# 3_MCU_EPS.net
KiCad netlist of a schematic drawn in Altium Designer
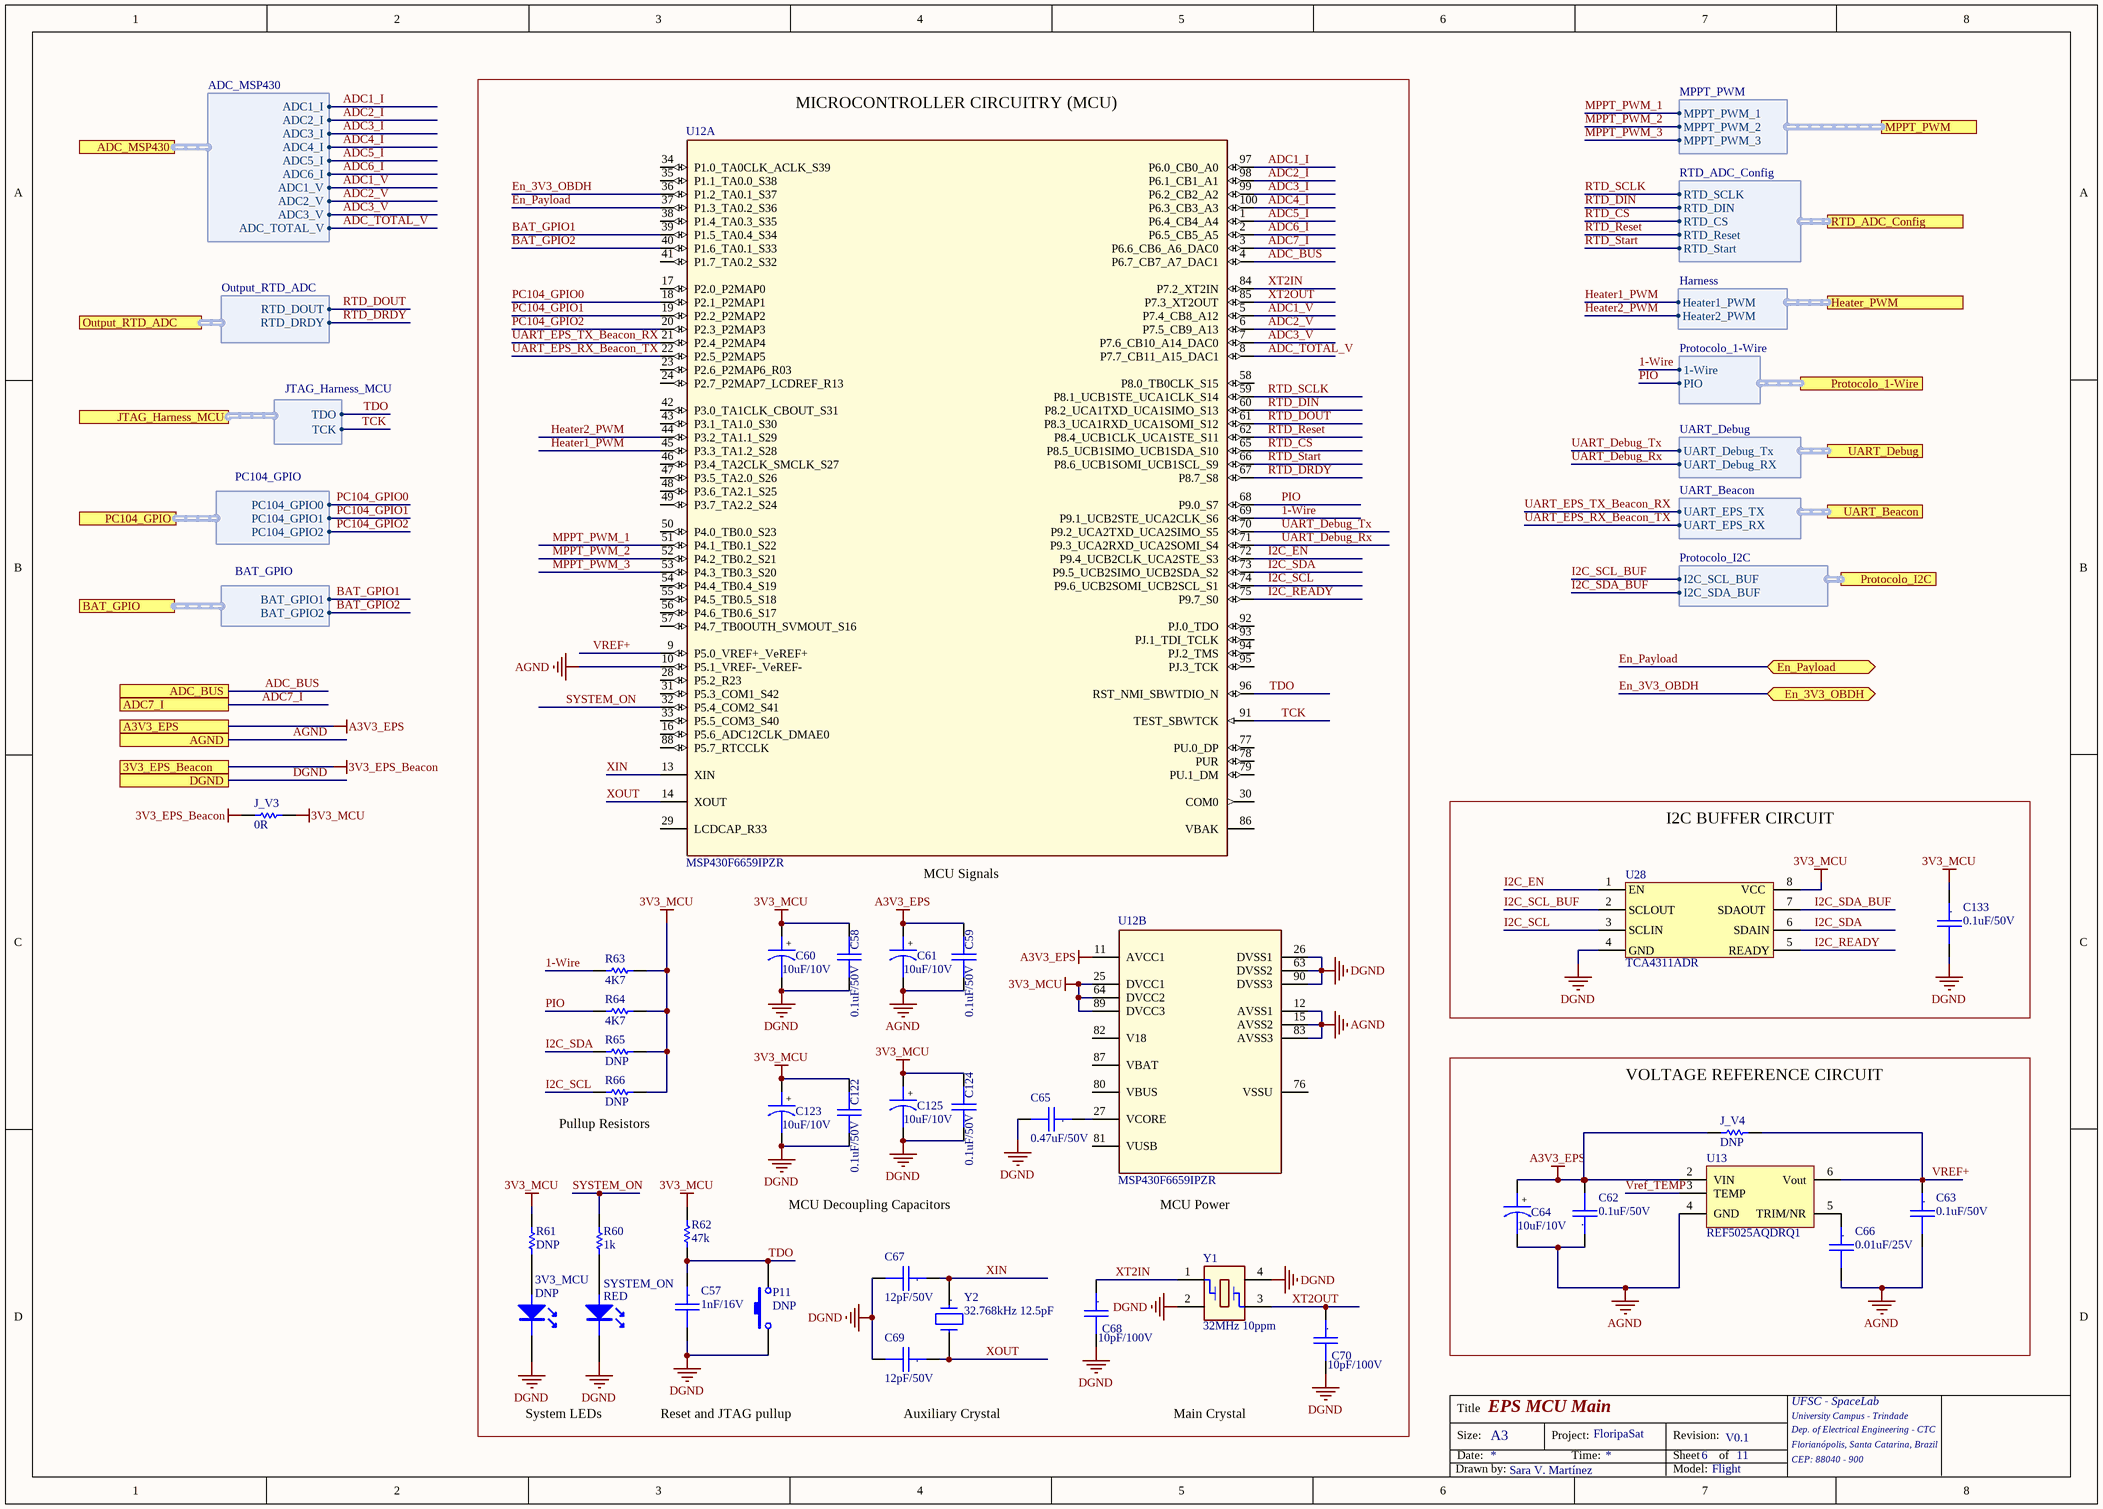
[diagram p0: 3_MCU_EPS.SchDoc]

(export (version "E")
  (design (tool "Eeschema 10.0.6"))
  (components
    (comp (ref "3V3_MCU")
      (value "DNP")
      (footprint "0603-LED")
      (description "SMD Green LED")
      (fields (field (name "PARTNUMBER") "150060VS75000"))
      (libsource (lib "FloripaSatSchlib") (part "LED/G_0603"))
    )
    (comp (ref "C57")
      (value "1nF/16V")
      (footprint "CC0805")
      (description "CAP CER 1nF 16V 0603 5%")
      (fields (field (name "PARTNUMBER") "C0603X102J4RECAUTO"))
      (libsource (lib "OBDH_Eng_Model_2_ALT") (part "Cap_Cer_X7R_1nF_16V_0603"))
    )
    (comp (ref "C58")
      (value "0.1uF/50V")
      (footprint "CC0603")
      (description "CAP CER 0.1UF 50V 10% X7R 0603")
      (fields (field (name "PARTNUMBER") "CC0603KPX7R9BB104"))
      (libsource (lib "PCB_Project_FlightModel_EPS") (part "Cap_Cer_X7R_0.1uF_50V_0603"))
    )
    (comp (ref "C59")
      (value "0.1uF/50V")
      (footprint "CC0603")
      (description "CAP CER 0.1UF 50V 10% X7R 0603")
      (fields (field (name "PARTNUMBER") "CC0603KPX7R9BB104"))
      (libsource (lib "PCB_Project_FlightModel_EPS") (part "Cap_Cer_X7R_0.1uF_50V_0603"))
    )
    (comp (ref "C60")
      (value "10uF/10V")
      (footprint "FloripaSatPcbLib:CC0805_Tantalum")
      (description "CAP Tantalum 10uF 6.3V 10% 0805")
      (fields (field (name "PARTNUMBER") "TPSR106K006R1000"))
      (libsource (lib "FloripaSatSchlib") (part "Cap_Tant_SMD_10uF_6V3_0805"))
    )
    (comp (ref "C61")
      (value "10uF/10V")
      (footprint "FloripaSatPcbLib:CC0805_Tantalum")
      (description "CAP Tantalum 10uF 6.3V 10% 0805")
      (fields (field (name "PARTNUMBER") "TPSR106K006R1000"))
      (libsource (lib "FloripaSatSchlib") (part "Cap_Tant_SMD_10uF_6V3_0805"))
    )
    (comp (ref "C62")
      (value "0.1uF/50V")
      (footprint "CC0805")
      (description "CAP CER 0.1UF 50V 10% X7R 0805")
      (fields (field (name "PARTNUMBER") "GRM188R71H104KA93D"))
      (libsource (lib "FloripaSatSchlib") (part "Cap_Cer_X7R_0.1uF_25V_0805"))
    )
    (comp (ref "C63")
      (value "0.1uF/50V")
      (footprint "CC0603")
      (description "CAP CER 0.1UF 50V 10% X7R 0603")
      (fields (field (name "PARTNUMBER") "CC0603KPX7R9BB104"))
      (libsource (lib "PCB_Project_FlightModel_EPS") (part "Cap_Cer_X7R_0.1uF_50V_0603"))
    )
    (comp (ref "C64")
      (value "10uF/10V")
      (footprint "FloripaSatPcbLib:CC0805_Tantalum")
      (description "CAP Tantalum 10uF 6.3V 10% 0805")
      (fields (field (name "PARTNUMBER") "TPSR106K006R1000"))
      (libsource (lib "FloripaSatSchlib") (part "Cap_Tant_SMD_10uF_6V3_0805"))
    )
    (comp (ref "C65")
      (value "0.47uF/50V")
      (footprint "CC0603")
      (description "CAP CER 0.47UF 50V 10% X7R 0603")
      (fields (field (name "PARTNUMBER") "C1608X7R1H474K080AE"))
      (libsource (lib "FloripaSatSchlib") (part "Cap_Cer_X7R_0.47uF_50V_0603"))
    )
    (comp (ref "C66")
      (value "0.01uF/25V")
      (footprint "CC0603")
      (description "CAP CER 0.01UF 25V 5% X7R 0603")
      (fields (field (name "PARTNUMBER") "06033C103JAT4A"))
      (libsource (lib "FloripaSatSchlib") (part "Cap_Cer_X7R_0.01uF_25V_0603"))
    )
    (comp (ref "C67")
      (value "12pF/50V")
      (footprint "CC0603")
      (description "CAP CER 12pF 50V 0603")
      (fields (field (name "PARTNUMBER") "GQM1885C1H120GB01D"))
      (libsource (lib "FloripaSatSchlib") (part "Cap_Cer_X7R_12pF_50V_0603"))
    )
    (comp (ref "C68")
      (value "10pF/100V")
      (footprint "CC0805")
      (description "CAP CER 10pF 100V 0805")
      (fields (field (name "PARTNUMBER") "08051A100FAT2A"))
      (libsource (lib "FloripaSatSchlib") (part "Cap_Cer_X7R_10pF_100V_0805"))
    )
    (comp (ref "C69")
      (value "12pF/50V")
      (footprint "CC0603")
      (description "CAP CER 12pF 50V 0603")
      (fields (field (name "PARTNUMBER") "GQM1885C1H120GB01D"))
      (libsource (lib "FloripaSatSchlib") (part "Cap_Cer_X7R_12pF_50V_0603"))
    )
    (comp (ref "C70")
      (value "10pF/100V")
      (footprint "CC0805")
      (description "CAP CER 10pF 100V 0805")
      (fields (field (name "PARTNUMBER") "08051A100FAT2A"))
      (libsource (lib "FloripaSatSchlib") (part "Cap_Cer_X7R_10pF_100V_0805"))
    )
    (comp (ref "C122")
      (value "0.1uF/50V")
      (footprint "CC0603")
      (description "CAP CER 0.1UF 50V 10% X7R 0603")
      (fields (field (name "PARTNUMBER") "CC0603KPX7R9BB104"))
      (libsource (lib "PCB_Project_FlightModel_EPS") (part "Cap_Cer_X7R_0.1uF_50V_0603"))
    )
    (comp (ref "C123")
      (value "10uF/10V")
      (footprint "FloripaSatPcbLib:CC0805_Tantalum")
      (description "CAP Tantalum 10uF 6.3V 10% 0805")
      (fields (field (name "PARTNUMBER") "TPSR106K006R1000"))
      (libsource (lib "FloripaSatSchlib") (part "Cap_Tant_SMD_10uF_6V3_0805"))
    )
    (comp (ref "C124")
      (value "0.1uF/50V")
      (footprint "CC0603")
      (description "CAP CER 0.1UF 50V 10% X7R 0603")
      (fields (field (name "PARTNUMBER") "CC0603KPX7R9BB104"))
      (libsource (lib "PCB_Project_FlightModel_EPS") (part "Cap_Cer_X7R_0.1uF_50V_0603"))
    )
    (comp (ref "C125")
      (value "10uF/10V")
      (footprint "FloripaSatPcbLib:CC0805_Tantalum")
      (description "CAP Tantalum 10uF 6.3V 10% 0805")
      (fields (field (name "PARTNUMBER") "TPSR106K006R1000"))
      (libsource (lib "FloripaSatSchlib") (part "Cap_Tant_SMD_10uF_6V3_0805"))
    )
    (comp (ref "C133")
      (value "0.1uF/50V")
      (footprint "CC0603")
      (description "CAP CER 0.1UF 50V 10% X7R 0603")
      (fields (field (name "PARTNUMBER") "CC0603KPX7R9BB104"))
      (libsource (lib "PCB_Project_FlightModel_EPS") (part "Cap_Cer_X7R_0.1uF_50V_0603"))
    )
    (comp (ref "J_V3")
      (value "0R")
      (footprint "0805")
      (description "RES 0R OHM 1/8W JUMPER 0805")
      (fields (field (name "PARTNUMBER") "CRCW08050000Z0EA"))
      (libsource (lib "PCB_Project_FlightModel_EPS") (part "R0R_JUMPER_1/8W_0805"))
    )
    (comp (ref "J_V4")
      (value "DNP")
      (footprint "0805")
      (description "RES 0R OHM 1/8W JUMPER 0805")
      (fields (field (name "PARTNUMBER") "CRCW08050000Z0EA"))
      (libsource (lib "PCB_Project_FlightModel_EPS") (part "R0R_JUMPER_1/8W_0805"))
    )
    (comp (ref "P11")
      (value "DNP")
      (footprint "B3U-1000P")
      (description "Tactile Switch SPST-NO Top Actuated Surface Mount 12V 0.05A")
      (fields (field (name "PARTNUMBER") "B3U-1000P") (field (name "MANUFACTURER") "TE Connectivity"))
      (libsource (lib "PCB_Project_FlightModel_EPS") (part "Tactile_Switches_B3U-1000P"))
    )
    (comp (ref "R60")
      (value "1k")
      (footprint "0603")
      (description "RES 1.0K OHM 1/8W 1% 0603")
      (fields (field (name "PARTNUMBER") "MCT06030C1001FP500"))
      (libsource (lib "FloripaSatSchlib") (part "R1.0k_1%_1/8W_0603"))
    )
    (comp (ref "R61")
      (value "DNP")
      (footprint "0603")
      (description "RES 1.0K OHM 1/8W 1% 0603")
      (fields (field (name "PARTNUMBER") "MCT06030C1001FP500"))
      (libsource (lib "FloripaSatSchlib") (part "R1.0k_1%_1/8W_0603"))
    )
    (comp (ref "R62")
      (value "47k")
      (footprint "0603")
      (description "RES 47K OHM 1/8W 0.5% 0603")
      (fields (field (name "PARTNUMBER") "MCT0603MD4702DP500"))
      (libsource (lib "FloripaSatSchlib") (part "R47k_1%_1/8W_0603"))
    )
    (comp (ref "R63")
      (value "4K7")
      (footprint "0603")
      (description "RES 4K7 OHM 1/8W 1% 0603")
      (fields (field (name "PARTNUMBER") "MCT06030C4701FP500"))
      (libsource (lib "FloripaSatSchlib") (part "R4.7K_1%_1/8W_0603"))
    )
    (comp (ref "R64")
      (value "4K7")
      (footprint "0603")
      (description "RES 4K7 OHM 1/8W 1% 0603")
      (fields (field (name "PARTNUMBER") "MCT06030C4701FP500"))
      (libsource (lib "FloripaSatSchlib") (part "R4.7K_1%_1/8W_0603"))
    )
    (comp (ref "R65")
      (value "DNP")
      (footprint "0603")
      (description "RES 10K OHM 1/8W 1%  0603")
      (fields (field (name "PARTNUMBER") "MCT0603MC1002FP500"))
      (libsource (lib "FloripaSatSchlib") (part "R10k_1%_1/8W_0603"))
    )
    (comp (ref "R66")
      (value "DNP")
      (footprint "0603")
      (description "RES 10K OHM 1/8W 1%  0603")
      (fields (field (name "PARTNUMBER") "MCT0603MC1002FP500"))
      (libsource (lib "FloripaSatSchlib") (part "R10k_1%_1/8W_0603"))
    )
    (comp (ref "SYSTEM_ON")
      (value "RED")
      (footprint "0603-LED")
      (description "SMD Red LED")
      (fields (field (name "PARTNUMBER") "LTST-C191KFKT"))
      (libsource (lib "FloripaSatSchlib") (part "LED/R_0603"))
    )
    (comp (ref "U12")
      (value "MSP430F6659IPZR")
      (footprint "PZ0100A_N")
      (description "Imported")
      (fields
        (field (name "ALTERNATE PARTNUMBER") "MSP430F6659IPZ")
        (field (name "MANUFACTURER") "Texas Instruments")
      )
      (libsource (lib "FloripaSatSchlib") (part "MSP430F6659IPZR"))
    )
    (comp (ref "U13")
      (value "REF5025AQDRQ1")
      (footprint "SOIC-8")
      (description "REF5025A-Q1")
      (libsource (lib "FloripaSatSchlib") (part "REF5025A-Q1"))
    )
    (comp (ref "U28")
      (value "TCA4311ADR")
      (footprint "SOIC8")
      (description "IC SIGNAL BUFFER I2C 8SOIC")
      (libsource (lib "PCB_Project_FlightModel_EPS") (part "TCA4311ADR"))
    )
    (comp (ref "Y1")
      (value "32MHz 10ppm")
      (footprint "XTAL_ABM8X")
      (description "32MHz ±10ppm Crystal 10pF 60 Ohm -40°C ~ 125°C")
      (fields (field (name "PARTNUMBER") "ABM8X-102-32.000MHZ-T"))
      (libsource (lib "FloripaSatSchlib") (part "XTAL_32MHz_SMD_4-SMD"))
    )
    (comp (ref "Y2")
      (value "32.768kHz 12.5pF")
      (footprint "ABS06 0805")
      (description "32.768kHz ±20ppm Crystal 12.5pF 70 kOhm -40°C ~ 125°C")
      (fields (field (name "PARTNUMBER") "ECS-.327-12.5-34S-TR"))
      (libsource (lib "FloripaSatSchlib") (part "Xtal_32.768kHz_12pF_2_SMD"))
    )
  )
  (nets
    (net (code "13") (name "/1-Wire") (class "Default")
      (node (ref "R63") (pin "2") (pinfunction "2_2") (pintype "passive"))
      (node (ref "U12") (pin "69") (pinfunction "P9.1_UCB2STE_UCA2CLK_S6_69") (pintype "bidirectional"))
    )
    (net (code "14") (name "/ADC1_I") (class "Default")
      (node (ref "U12") (pin "97") (pinfunction "P6.0_CB0_A0_97") (pintype "bidirectional"))
    )
    (net (code "15") (name "/ADC1_V") (class "Default")
      (node (ref "U12") (pin "5") (pinfunction "P7.4_CB8_A12_5") (pintype "bidirectional"))
    )
    (net (code "16") (name "/ADC2_I") (class "Default")
      (node (ref "U12") (pin "98") (pinfunction "P6.1_CB1_A1_98") (pintype "bidirectional"))
    )
    (net (code "17") (name "/ADC2_V") (class "Default")
      (node (ref "U12") (pin "6") (pinfunction "P7.5_CB9_A13_6") (pintype "bidirectional"))
    )
    (net (code "18") (name "/ADC3_I") (class "Default")
      (node (ref "U12") (pin "99") (pinfunction "P6.2_CB2_A2_99") (pintype "bidirectional"))
    )
    (net (code "19") (name "/ADC3_V") (class "Default")
      (node (ref "U12") (pin "7") (pinfunction "P7.6_CB10_A14_DAC0_7") (pintype "bidirectional"))
    )
    (net (code "20") (name "/ADC4_I") (class "Default")
      (node (ref "U12") (pin "100") (pinfunction "P6.3_CB3_A3_100") (pintype "bidirectional"))
    )
    (net (code "21") (name "/ADC5_I") (class "Default")
      (node (ref "U12") (pin "1") (pinfunction "P6.4_CB4_A4_1") (pintype "bidirectional"))
    )
    (net (code "22") (name "/ADC6_I") (class "Default")
      (node (ref "U12") (pin "2") (pinfunction "P6.5_CB5_A5_2") (pintype "bidirectional"))
    )
    (net (code "23") (name "/ADC7_I") (class "Default")
      (node (ref "U12") (pin "3") (pinfunction "P6.6_CB6_A6_DAC0_3") (pintype "bidirectional"))
    )
    (net (code "24") (name "/ADC_BUS") (class "Default")
      (node (ref "U12") (pin "4") (pinfunction "P6.7_CB7_A7_DAC1_4") (pintype "bidirectional"))
    )
    (net (code "25") (name "/ADC_TOTAL_V") (class "Default")
      (node (ref "U12") (pin "8") (pinfunction "P7.7_CB11_A15_DAC1_8") (pintype "bidirectional"))
    )
    (net (code "26") (name "/BAT_GPIO1") (class "Default")
      (node (ref "U12") (pin "39") (pinfunction "P1.5_TA0.4_S34_39") (pintype "bidirectional"))
    )
    (net (code "27") (name "/BAT_GPIO2") (class "Default")
      (node (ref "U12") (pin "40") (pinfunction "P1.6_TA0.1_S33_40") (pintype "bidirectional"))
    )
    (net (code "28") (name "/En_3V3_OBDH") (class "Default")
      (node (ref "U12") (pin "36") (pinfunction "P1.2_TA0.1_S37_36") (pintype "bidirectional"))
    )
    (net (code "29") (name "/En_Payload") (class "Default")
      (node (ref "U12") (pin "37") (pinfunction "P1.3_TA0.2_S36_37") (pintype "bidirectional"))
    )
    (net (code "30") (name "/Heater1_PWM") (class "Default")
      (node (ref "U12") (pin "45") (pinfunction "P3.3_TA1.2_S28_45") (pintype "bidirectional"))
    )
    (net (code "31") (name "/Heater2_PWM") (class "Default")
      (node (ref "U12") (pin "44") (pinfunction "P3.2_TA1.1_S29_44") (pintype "bidirectional"))
    )
    (net (code "32") (name "/I2C_EN") (class "Default")
      (node (ref "U12") (pin "72") (pinfunction "P9.4_UCB2CLK_UCA2STE_S3_72") (pintype "bidirectional"))
      (node (ref "U28") (pin "1") (pinfunction "EN_1") (pintype "passive"))
    )
    (net (code "33") (name "/I2C_READY") (class "Default")
      (node (ref "U12") (pin "75") (pinfunction "P9.7_S0_75") (pintype "bidirectional"))
      (node (ref "U28") (pin "5") (pinfunction "READY_5") (pintype "passive"))
    )
    (net (code "34") (name "/I2C_SCL") (class "Default")
      (node (ref "R66") (pin "2") (pinfunction "2_2") (pintype "passive"))
      (node (ref "U12") (pin "74") (pinfunction "P9.6_UCB2SOMI_UCB2SCL_S1_74") (pintype "bidirectional"))
      (node (ref "U28") (pin "3") (pinfunction "SCLIN_3") (pintype "passive"))
    )
    (net (code "35") (name "/I2C_SCL_BUF") (class "Default")
      (node (ref "U28") (pin "2") (pinfunction "SCLOUT_2") (pintype "passive"))
    )
    (net (code "36") (name "/I2C_SDA") (class "Default")
      (node (ref "R65") (pin "2") (pinfunction "2_2") (pintype "passive"))
      (node (ref "U12") (pin "73") (pinfunction "P9.5_UCB2SIMO_UCB2SDA_S2_73") (pintype "bidirectional"))
      (node (ref "U28") (pin "6") (pinfunction "SDAIN_6") (pintype "passive"))
    )
    (net (code "37") (name "/I2C_SDA_BUF") (class "Default")
      (node (ref "U28") (pin "7") (pinfunction "SDAOUT_7") (pintype "passive"))
    )
    (net (code "38") (name "/MPPT_PWM_1") (class "Default")
      (node (ref "U12") (pin "51") (pinfunction "P4.1_TB0.1_S22_51") (pintype "bidirectional"))
    )
    (net (code "39") (name "/MPPT_PWM_2") (class "Default")
      (node (ref "U12") (pin "52") (pinfunction "P4.2_TB0.2_S21_52") (pintype "bidirectional"))
    )
    (net (code "40") (name "/MPPT_PWM_3") (class "Default")
      (node (ref "U12") (pin "53") (pinfunction "P4.3_TB0.3_S20_53") (pintype "bidirectional"))
    )
    (net (code "41") (name "/PC104_GPIO0") (class "Default")
      (node (ref "U12") (pin "18") (pinfunction "P2.1_P2MAP1_18") (pintype "bidirectional"))
    )
    (net (code "42") (name "/PC104_GPIO1") (class "Default")
      (node (ref "U12") (pin "19") (pinfunction "P2.2_P2MAP2_19") (pintype "bidirectional"))
    )
    (net (code "43") (name "/PC104_GPIO2") (class "Default")
      (node (ref "U12") (pin "20") (pinfunction "P2.3_P2MAP3_20") (pintype "bidirectional"))
    )
    (net (code "44") (name "/PIO") (class "Default")
      (node (ref "R64") (pin "2") (pinfunction "2_2") (pintype "passive"))
      (node (ref "U12") (pin "68") (pinfunction "P9.0_S7_68") (pintype "bidirectional"))
    )
    (net (code "45") (name "/RTD_CS") (class "Default")
      (node (ref "U12") (pin "65") (pinfunction "P8.5_UCB1SIMO_UCB1SDA_S10_65") (pintype "bidirectional"))
    )
    (net (code "46") (name "/RTD_DIN") (class "Default")
      (node (ref "U12") (pin "60") (pinfunction "P8.2_UCA1TXD_UCA1SIMO_S13_60") (pintype "bidirectional"))
    )
    (net (code "47") (name "/RTD_DOUT") (class "Default")
      (node (ref "U12") (pin "61") (pinfunction "P8.3_UCA1RXD_UCA1SOMI_S12_61") (pintype "bidirectional"))
    )
    (net (code "48") (name "/RTD_DRDY") (class "Default")
      (node (ref "U12") (pin "67") (pinfunction "P8.7_S8_67") (pintype "bidirectional"))
    )
    (net (code "49") (name "/RTD_Reset") (class "Default")
      (node (ref "U12") (pin "62") (pinfunction "P8.4_UCB1CLK_UCA1STE_S11_62") (pintype "bidirectional"))
    )
    (net (code "50") (name "/RTD_SCLK") (class "Default")
      (node (ref "U12") (pin "59") (pinfunction "P8.1_UCB1STE_UCA1CLK_S14_59") (pintype "bidirectional"))
    )
    (net (code "51") (name "/RTD_Start") (class "Default")
      (node (ref "U12") (pin "66") (pinfunction "P8.6_UCB1SOMI_UCB1SCL_S9_66") (pintype "bidirectional"))
    )
    (net (code "52") (name "/SYSTEM_ON") (class "Default")
      (node (ref "R60") (pin "2") (pinfunction "2_2") (pintype "passive"))
      (node (ref "U12") (pin "32") (pinfunction "P5.4_COM2_S41_32") (pintype "bidirectional"))
    )
    (net (code "53") (name "/TCK") (class "Default")
      (node (ref "U12") (pin "91") (pinfunction "TEST_SBWTCK_91") (pintype "input"))
    )
    (net (code "54") (name "/TDO") (class "Default")
      (node (ref "C57") (pin "1") (pinfunction "1_1") (pintype "passive"))
      (node (ref "P11") (pin "2") (pinfunction "2_2") (pintype "passive"))
      (node (ref "R62") (pin "1") (pinfunction "1_1") (pintype "passive"))
      (node (ref "U12") (pin "96") (pinfunction "RST_NMI_SBWTDIO_N_96") (pintype "bidirectional"))
    )
    (net (code "55") (name "/UART_Debug_Rx") (class "Default")
      (node (ref "U12") (pin "71") (pinfunction "P9.3_UCA2RXD_UCA2SOMI_S4_71") (pintype "bidirectional"))
    )
    (net (code "56") (name "/UART_Debug_Tx") (class "Default")
      (node (ref "U12") (pin "70") (pinfunction "P9.2_UCA2TXD_UCA2SIMO_S5_70") (pintype "bidirectional"))
    )
    (net (code "57") (name "/UART_EPS_RX_Beacon_TX") (class "Default")
      (node (ref "U12") (pin "22") (pinfunction "P2.5_P2MAP5_22") (pintype "bidirectional"))
    )
    (net (code "58") (name "/UART_EPS_TX_Beacon_RX") (class "Default")
      (node (ref "U12") (pin "21") (pinfunction "P2.4_P2MAP4_21") (pintype "bidirectional"))
    )
    (net (code "59") (name "/VREF+") (class "Default")
      (node (ref "C63") (pin "1") (pinfunction "1_1") (pintype "passive"))
      (node (ref "J_V4") (pin "1") (pinfunction "1_1") (pintype "passive"))
      (node (ref "U12") (pin "9") (pinfunction "P5.0_VREF+_VeREF+_9") (pintype "bidirectional"))
      (node (ref "U13") (pin "6") (pinfunction "Vout_6") (pintype "passive"))
    )
    (net (code "60") (name "/Vref_TEMP") (class "Default")
      (node (ref "U13") (pin "3") (pinfunction "TEMP_3") (pintype "passive"))
    )
    (net (code "61") (name "/XIN") (class "Default")
      (node (ref "C67") (pin "1") (pinfunction "1_1") (pintype "passive"))
      (node (ref "U12") (pin "13") (pinfunction "XIN_13") (pintype "passive"))
      (node (ref "Y2") (pin "1") (pinfunction "1_1") (pintype "passive"))
    )
    (net (code "62") (name "/XOUT") (class "Default")
      (node (ref "C69") (pin "1") (pinfunction "1_1") (pintype "passive"))
      (node (ref "U12") (pin "14") (pinfunction "XOUT_14") (pintype "passive"))
      (node (ref "Y2") (pin "2") (pinfunction "2_2") (pintype "passive"))
    )
    (net (code "63") (name "/XT2IN") (class "Default")
      (node (ref "C68") (pin "1") (pinfunction "1_1") (pintype "passive"))
      (node (ref "U12") (pin "84") (pinfunction "P7.2_XT2IN_84") (pintype "bidirectional"))
      (node (ref "Y1") (pin "1") (pinfunction "1_1") (pintype "passive"))
    )
    (net (code "64") (name "/XT2OUT") (class "Default")
      (node (ref "C70") (pin "1") (pinfunction "1_1") (pintype "passive"))
      (node (ref "U12") (pin "85") (pinfunction "P7.3_XT2OUT_85") (pintype "bidirectional"))
      (node (ref "Y1") (pin "3") (pinfunction "3_3") (pintype "passive"))
    )
    (net (code "77") (name "3V3_EPS_Beacon") (class "Default")
      (node (ref "J_V3") (pin "2") (pinfunction "2_2") (pintype "passive"))
    )
    (net (code "78") (name "3V3_MCU") (class "Default")
      (node (ref "C122") (pin "1") (pinfunction "1_1") (pintype "passive"))
      (node (ref "C123") (pin "1") (pinfunction "1_1") (pintype "passive"))
      (node (ref "C124") (pin "1") (pinfunction "1_1") (pintype "passive"))
      (node (ref "C125") (pin "1") (pinfunction "1_1") (pintype "passive"))
      (node (ref "C133") (pin "1") (pinfunction "1_1") (pintype "passive"))
      (node (ref "C58") (pin "1") (pinfunction "1_1") (pintype "passive"))
      (node (ref "C60") (pin "1") (pinfunction "1_1") (pintype "passive"))
      (node (ref "J_V3") (pin "1") (pinfunction "1_1") (pintype "passive"))
      (node (ref "R61") (pin "2") (pinfunction "2_2") (pintype "passive"))
      (node (ref "R62") (pin "2") (pinfunction "2_2") (pintype "passive"))
      (node (ref "R63") (pin "1") (pinfunction "1_1") (pintype "passive"))
      (node (ref "R64") (pin "1") (pinfunction "1_1") (pintype "passive"))
      (node (ref "R65") (pin "1") (pinfunction "1_1") (pintype "passive"))
      (node (ref "R66") (pin "1") (pinfunction "1_1") (pintype "passive"))
      (node (ref "U12") (pin "25") (pinfunction "DVCC1_25") (pintype "power_in"))
      (node (ref "U12") (pin "64") (pinfunction "DVCC2_64") (pintype "power_in"))
      (node (ref "U12") (pin "89") (pinfunction "DVCC3_89") (pintype "power_in"))
      (node (ref "U28") (pin "8") (pinfunction "VCC_8") (pintype "power_in"))
    )
    (net (code "79") (name "A3V3_EPS") (class "Default")
      (node (ref "C59") (pin "1") (pinfunction "1_1") (pintype "passive"))
      (node (ref "C61") (pin "1") (pinfunction "1_1") (pintype "passive"))
      (node (ref "C62") (pin "2") (pinfunction "2_2") (pintype "passive"))
      (node (ref "C64") (pin "1") (pinfunction "1_1") (pintype "passive"))
      (node (ref "J_V4") (pin "2") (pinfunction "2_2") (pintype "passive"))
      (node (ref "U12") (pin "11") (pinfunction "AVCC1_11") (pintype "power_in"))
      (node (ref "U13") (pin "2") (pinfunction "VIN_2") (pintype "passive"))
    )
    (net (code "80") (name "AGND") (class "Default")
      (node (ref "C59") (pin "2") (pinfunction "2_2") (pintype "passive"))
      (node (ref "C61") (pin "2") (pinfunction "2_2") (pintype "passive"))
      (node (ref "C62") (pin "1") (pinfunction "1_1") (pintype "passive"))
      (node (ref "C63") (pin "2") (pinfunction "2_2") (pintype "passive"))
      (node (ref "C64") (pin "2") (pinfunction "2_2") (pintype "passive"))
      (node (ref "C66") (pin "2") (pinfunction "2_2") (pintype "passive"))
      (node (ref "U12") (pin "10") (pinfunction "P5.1_VREF-_VeREF-_10") (pintype "bidirectional"))
      (node (ref "U12") (pin "12") (pinfunction "AVSS1_12") (pintype "power_in"))
      (node (ref "U12") (pin "15") (pinfunction "AVSS2_15") (pintype "power_in"))
      (node (ref "U12") (pin "83") (pinfunction "AVSS3_83") (pintype "power_in"))
      (node (ref "U13") (pin "4") (pinfunction "GND_4") (pintype "passive"))
    )
    (net (code "81") (name "DGND") (class "Default")
      (node (ref "3V3_MCU") (pin "2") (pinfunction "K_2") (pintype "passive"))
      (node (ref "C122") (pin "2") (pinfunction "2_2") (pintype "passive"))
      (node (ref "C123") (pin "2") (pinfunction "2_2") (pintype "passive"))
      (node (ref "C124") (pin "2") (pinfunction "2_2") (pintype "passive"))
      (node (ref "C125") (pin "2") (pinfunction "2_2") (pintype "passive"))
      (node (ref "C133") (pin "2") (pinfunction "2_2") (pintype "passive"))
      (node (ref "C57") (pin "2") (pinfunction "2_2") (pintype "passive"))
      (node (ref "C58") (pin "2") (pinfunction "2_2") (pintype "passive"))
      (node (ref "C60") (pin "2") (pinfunction "2_2") (pintype "passive"))
      (node (ref "C65") (pin "2") (pinfunction "2_2") (pintype "passive"))
      (node (ref "C67") (pin "2") (pinfunction "2_2") (pintype "passive"))
      (node (ref "C68") (pin "2") (pinfunction "2_2") (pintype "passive"))
      (node (ref "C69") (pin "2") (pinfunction "2_2") (pintype "passive"))
      (node (ref "C70") (pin "2") (pinfunction "2_2") (pintype "passive"))
      (node (ref "P11") (pin "1") (pinfunction "1_1") (pintype "passive"))
      (node (ref "SYSTEM_ON") (pin "2") (pinfunction "K_2") (pintype "passive"))
      (node (ref "U12") (pin "26") (pinfunction "DVSS1_26") (pintype "power_in"))
      (node (ref "U12") (pin "63") (pinfunction "DVSS2_63") (pintype "power_in"))
      (node (ref "U12") (pin "90") (pinfunction "DVSS3_90") (pintype "power_in"))
      (node (ref "U28") (pin "4") (pinfunction "GND_4") (pintype "passive"))
      (node (ref "Y1") (pin "2") (pinfunction "2_2") (pintype "passive"))
      (node (ref "Y1") (pin "4") (pinfunction "4_4") (pintype "passive"))
    )
    (net (code "82") (name "Net-(3V3_MCU-A)") (class "Default")
      (node (ref "3V3_MCU") (pin "1") (pinfunction "A_1") (pintype "passive"))
      (node (ref "R61") (pin "1") (pinfunction "1_1") (pintype "passive"))
    )
    (net (code "83") (name "Net-(SYSTEM_ON-A)") (class "Default")
      (node (ref "R60") (pin "1") (pinfunction "1_1") (pintype "passive"))
      (node (ref "SYSTEM_ON") (pin "1") (pinfunction "A_1") (pintype "passive"))
    )
    (net (code "84") (name "Net-(U12B-VCORE)") (class "Default")
      (node (ref "C65") (pin "1") (pinfunction "1_1") (pintype "passive"))
      (node (ref "U12") (pin "27") (pinfunction "VCORE_27") (pintype "power_in"))
    )
    (net (code "85") (name "Net-(U13-TRIM{slash}NR)") (class "Default")
      (node (ref "C66") (pin "1") (pinfunction "1_1") (pintype "passive"))
      (node (ref "U13") (pin "5") (pinfunction "TRIM/NR_5") (pintype "passive"))
    )
    (net (code "86") (name "unconnected-(U12A-COM0-Pad30)") (class "Default")
      (node (ref "U12") (pin "30") (pinfunction "COM0_30") (pintype "output"))
    )
    (net (code "87") (name "unconnected-(U12A-LCDCAP_R33-Pad29)") (class "Default")
      (node (ref "U12") (pin "29") (pinfunction "LCDCAP_R33_29") (pintype "passive"))
    )
    (net (code "88") (name "unconnected-(U12A-P1.0_TA0CLK_ACLK_S39-Pad34)") (class "Default")
      (node (ref "U12") (pin "34") (pinfunction "P1.0_TA0CLK_ACLK_S39_34") (pintype "bidirectional"))
    )
    (net (code "89") (name "unconnected-(U12A-P1.1_TA0.0_S38-Pad35)") (class "Default")
      (node (ref "U12") (pin "35") (pinfunction "P1.1_TA0.0_S38_35") (pintype "bidirectional"))
    )
    (net (code "90") (name "unconnected-(U12A-P1.4_TA0.3_S35-Pad38)") (class "Default")
      (node (ref "U12") (pin "38") (pinfunction "P1.4_TA0.3_S35_38") (pintype "bidirectional"))
    )
    (net (code "91") (name "unconnected-(U12A-P1.7_TA0.2_S32-Pad41)") (class "Default")
      (node (ref "U12") (pin "41") (pinfunction "P1.7_TA0.2_S32_41") (pintype "bidirectional"))
    )
    (net (code "92") (name "unconnected-(U12A-P2.0_P2MAP0-Pad17)") (class "Default")
      (node (ref "U12") (pin "17") (pinfunction "P2.0_P2MAP0_17") (pintype "bidirectional"))
    )
    (net (code "93") (name "unconnected-(U12A-P2.6_P2MAP6_R03-Pad23)") (class "Default")
      (node (ref "U12") (pin "23") (pinfunction "P2.6_P2MAP6_R03_23") (pintype "bidirectional"))
    )
    (net (code "94") (name "unconnected-(U12A-P2.7_P2MAP7_LCDREF_R13-Pad24)") (class "Default")
      (node (ref "U12") (pin "24") (pinfunction "P2.7_P2MAP7_LCDREF_R13_24") (pintype "bidirectional"))
    )
    (net (code "95") (name "unconnected-(U12A-P3.0_TA1CLK_CBOUT_S31-Pad42)") (class "Default")
      (node (ref "U12") (pin "42") (pinfunction "P3.0_TA1CLK_CBOUT_S31_42") (pintype "bidirectional"))
    )
    (net (code "96") (name "unconnected-(U12A-P3.1_TA1.0_S30-Pad43)") (class "Default")
      (node (ref "U12") (pin "43") (pinfunction "P3.1_TA1.0_S30_43") (pintype "bidirectional"))
    )
    (net (code "97") (name "unconnected-(U12A-P3.4_TA2CLK_SMCLK_S27-Pad46)") (class "Default")
      (node (ref "U12") (pin "46") (pinfunction "P3.4_TA2CLK_SMCLK_S27_46") (pintype "bidirectional"))
    )
    (net (code "98") (name "unconnected-(U12A-P3.5_TA2.0_S26-Pad47)") (class "Default")
      (node (ref "U12") (pin "47") (pinfunction "P3.5_TA2.0_S26_47") (pintype "bidirectional"))
    )
    (net (code "99") (name "unconnected-(U12A-P3.6_TA2.1_S25-Pad48)") (class "Default")
      (node (ref "U12") (pin "48") (pinfunction "P3.6_TA2.1_S25_48") (pintype "bidirectional"))
    )
    (net (code "100") (name "unconnected-(U12A-P3.7_TA2.2_S24-Pad49)") (class "Default")
      (node (ref "U12") (pin "49") (pinfunction "P3.7_TA2.2_S24_49") (pintype "bidirectional"))
    )
    (net (code "101") (name "unconnected-(U12A-P4.0_TB0.0_S23-Pad50)") (class "Default")
      (node (ref "U12") (pin "50") (pinfunction "P4.0_TB0.0_S23_50") (pintype "bidirectional"))
    )
    (net (code "102") (name "unconnected-(U12A-P4.4_TB0.4_S19-Pad54)") (class "Default")
      (node (ref "U12") (pin "54") (pinfunction "P4.4_TB0.4_S19_54") (pintype "bidirectional"))
    )
    (net (code "103") (name "unconnected-(U12A-P4.5_TB0.5_S18-Pad55)") (class "Default")
      (node (ref "U12") (pin "55") (pinfunction "P4.5_TB0.5_S18_55") (pintype "bidirectional"))
    )
    (net (code "104") (name "unconnected-(U12A-P4.6_TB0.6_S17-Pad56)") (class "Default")
      (node (ref "U12") (pin "56") (pinfunction "P4.6_TB0.6_S17_56") (pintype "bidirectional"))
    )
    (net (code "105") (name "unconnected-(U12A-P4.7_TB0OUTH_SVMOUT_S16-Pad57)") (class "Default")
      (node (ref "U12") (pin "57") (pinfunction "P4.7_TB0OUTH_SVMOUT_S16_57") (pintype "bidirectional"))
    )
    (net (code "106") (name "unconnected-(U12A-P5.2_R23-Pad28)") (class "Default")
      (node (ref "U12") (pin "28") (pinfunction "P5.2_R23_28") (pintype "bidirectional"))
    )
    (net (code "107") (name "unconnected-(U12A-P5.3_COM1_S42-Pad31)") (class "Default")
      (node (ref "U12") (pin "31") (pinfunction "P5.3_COM1_S42_31") (pintype "bidirectional"))
    )
    (net (code "108") (name "unconnected-(U12A-P5.5_COM3_S40-Pad33)") (class "Default")
      (node (ref "U12") (pin "33") (pinfunction "P5.5_COM3_S40_33") (pintype "bidirectional"))
    )
    (net (code "109") (name "unconnected-(U12A-P5.6_ADC12CLK_DMAE0-Pad16)") (class "Default")
      (node (ref "U12") (pin "16") (pinfunction "P5.6_ADC12CLK_DMAE0_16") (pintype "bidirectional"))
    )
    (net (code "110") (name "unconnected-(U12A-P5.7_RTCCLK-Pad88)") (class "Default")
      (node (ref "U12") (pin "88") (pinfunction "P5.7_RTCCLK_88") (pintype "bidirectional"))
    )
    (net (code "111") (name "unconnected-(U12A-P8.0_TB0CLK_S15-Pad58)") (class "Default")
      (node (ref "U12") (pin "58") (pinfunction "P8.0_TB0CLK_S15_58") (pintype "bidirectional"))
    )
    (net (code "112") (name "unconnected-(U12A-PJ.0_TDO-Pad92)") (class "Default")
      (node (ref "U12") (pin "92") (pinfunction "PJ.0_TDO_92") (pintype "bidirectional"))
    )
    (net (code "113") (name "unconnected-(U12A-PJ.1_TDI_TCLK-Pad93)") (class "Default")
      (node (ref "U12") (pin "93") (pinfunction "PJ.1_TDI_TCLK_93") (pintype "bidirectional"))
    )
    (net (code "114") (name "unconnected-(U12A-PJ.2_TMS-Pad94)") (class "Default")
      (node (ref "U12") (pin "94") (pinfunction "PJ.2_TMS_94") (pintype "bidirectional"))
    )
    (net (code "115") (name "unconnected-(U12A-PJ.3_TCK-Pad95)") (class "Default")
      (node (ref "U12") (pin "95") (pinfunction "PJ.3_TCK_95") (pintype "bidirectional"))
    )
    (net (code "116") (name "unconnected-(U12A-PU.0_DP-Pad77)") (class "Default")
      (node (ref "U12") (pin "77") (pinfunction "PU.0_DP_77") (pintype "bidirectional"))
    )
    (net (code "117") (name "unconnected-(U12A-PU.1_DM-Pad79)") (class "Default")
      (node (ref "U12") (pin "79") (pinfunction "PU.1_DM_79") (pintype "bidirectional"))
    )
    (net (code "118") (name "unconnected-(U12A-PUR-Pad78)") (class "Default")
      (node (ref "U12") (pin "78") (pinfunction "PUR_78") (pintype "bidirectional"))
    )
    (net (code "119") (name "unconnected-(U12A-VBAK-Pad86)") (class "Default")
      (node (ref "U12") (pin "86") (pinfunction "VBAK_86") (pintype "passive"))
    )
    (net (code "120") (name "unconnected-(U12B-V18-Pad82)") (class "Default")
      (node (ref "U12") (pin "82") (pinfunction "V18_82") (pintype "power_in"))
    )
    (net (code "121") (name "unconnected-(U12B-VBAT-Pad87)") (class "Default")
      (node (ref "U12") (pin "87") (pinfunction "VBAT_87") (pintype "power_in"))
    )
    (net (code "122") (name "unconnected-(U12B-VBUS-Pad80)") (class "Default")
      (node (ref "U12") (pin "80") (pinfunction "VBUS_80") (pintype "power_in"))
    )
    (net (code "123") (name "unconnected-(U12B-VSSU-Pad76)") (class "Default")
      (node (ref "U12") (pin "76") (pinfunction "VSSU_76") (pintype "power_in"))
    )
    (net (code "124") (name "unconnected-(U12B-VUSB-Pad81)") (class "Default")
      (node (ref "U12") (pin "81") (pinfunction "VUSB_81") (pintype "power_in"))
    )
  )
)
